# application.net
KiCad netlist of a schematic drawn in EAGLE
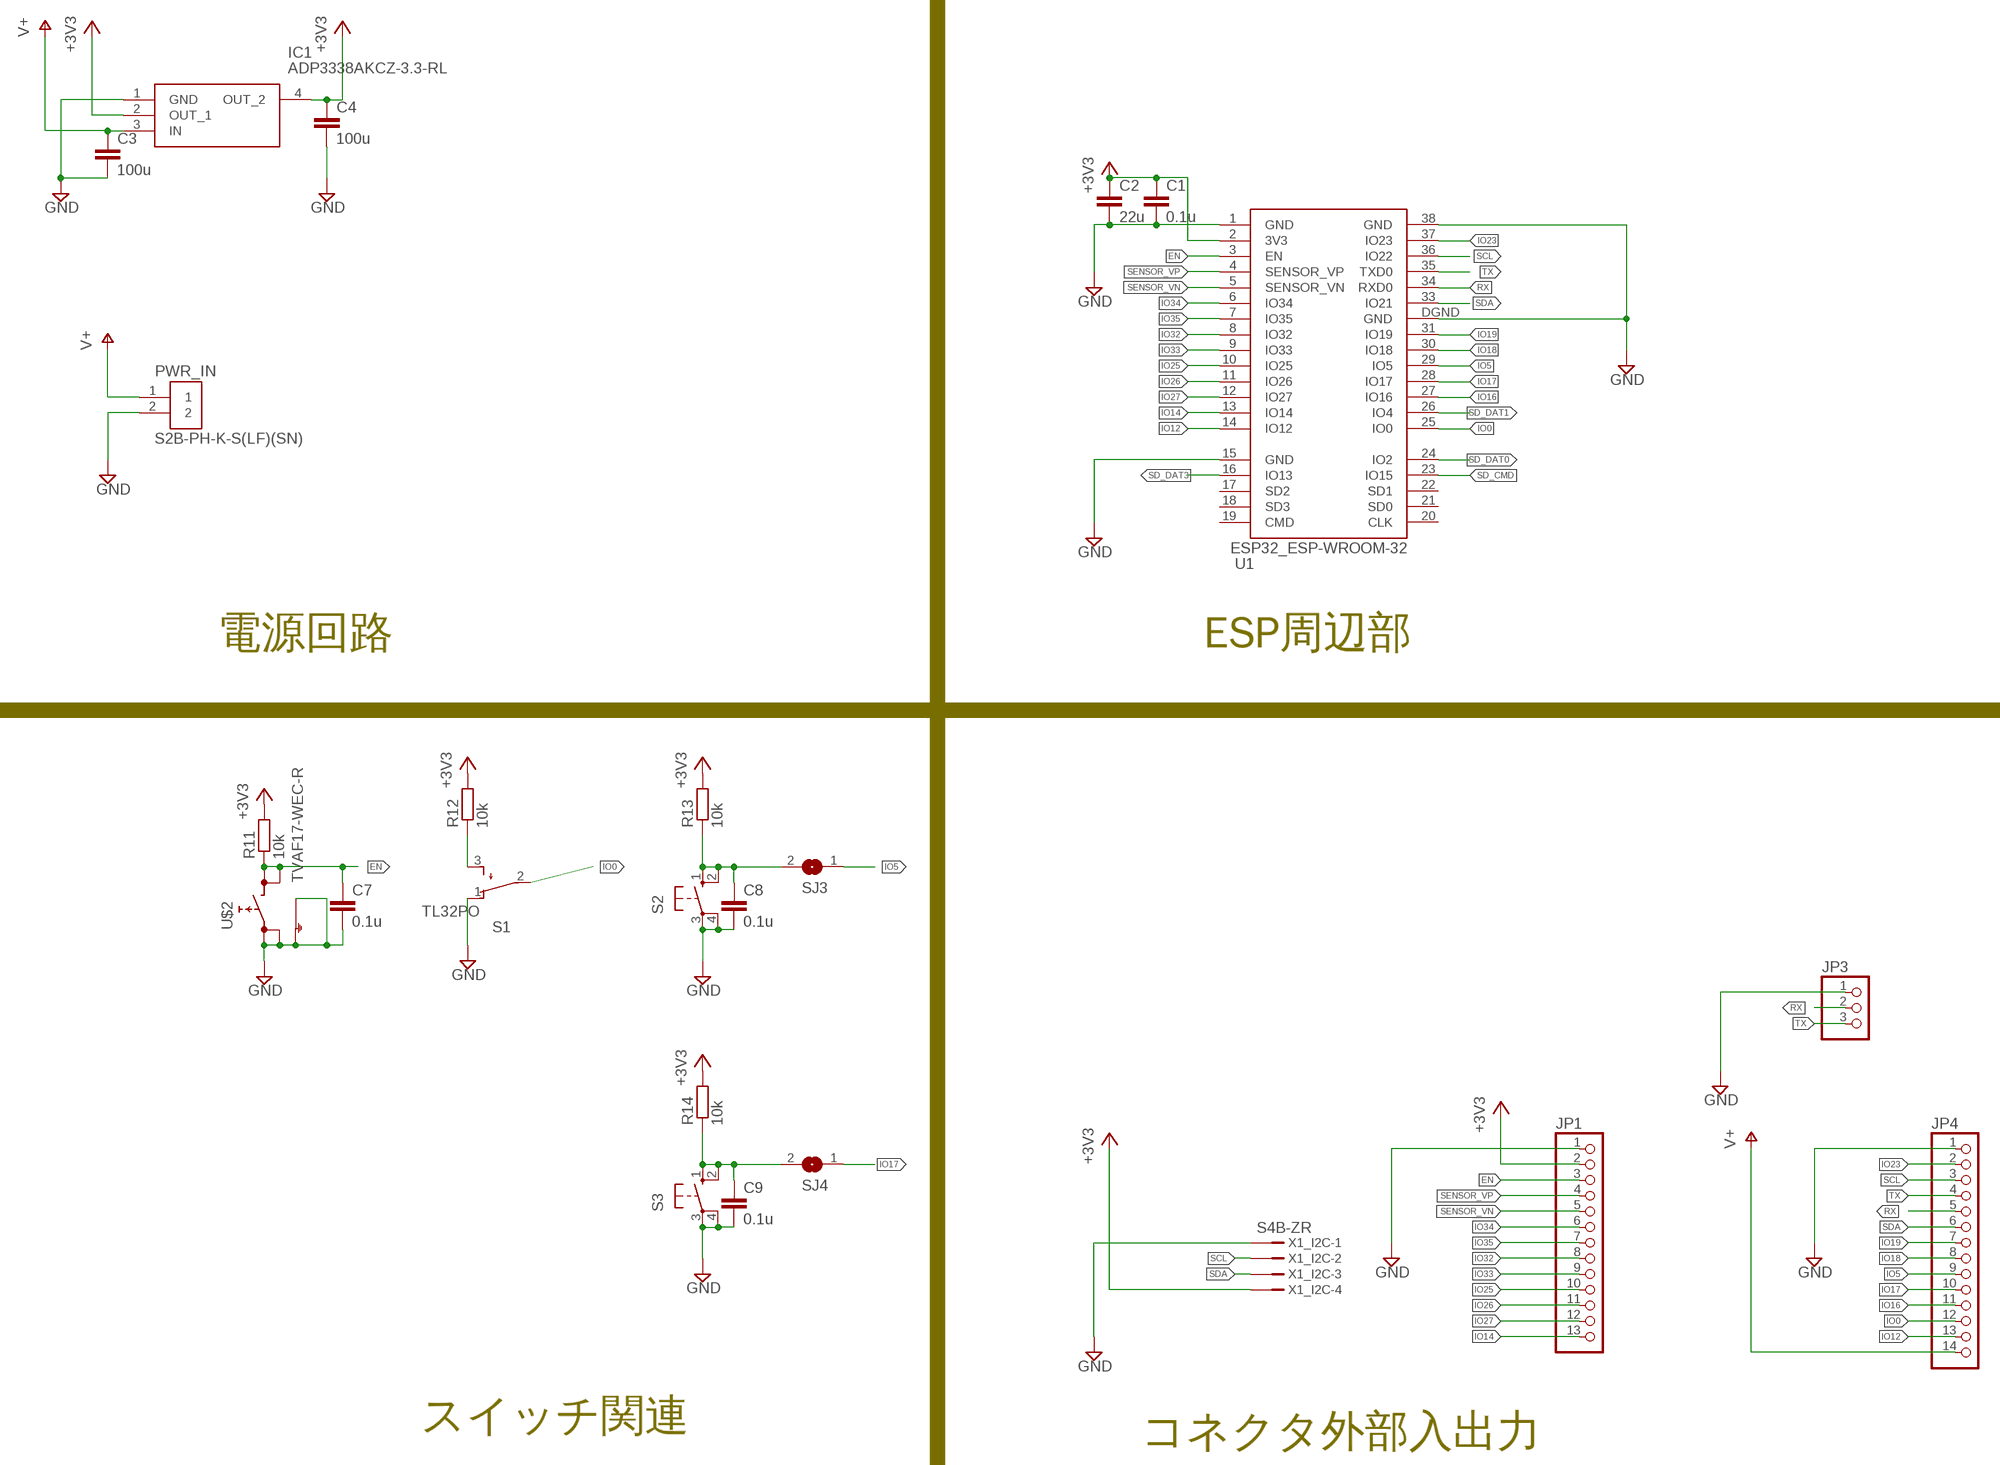
[diagram p0: schematic, sheet 1]

(export (version "E")
  (design (tool "Eeschema 10.0.6"))
  (components
    (comp (ref "C1")
      (value "0.1u")
      (footprint "eagle-import:C0603K")
      (libsource (lib "eagle-import") (part "C-EUC0603K"))
    )
    (comp (ref "C2")
      (value "22u")
      (footprint "eagle-import:C0805")
      (libsource (lib "eagle-import") (part "C-EUC0805"))
    )
    (comp (ref "C3")
      (value "100u")
      (footprint "eagle-import:C1206")
      (libsource (lib "eagle-import") (part "C-EUC1206"))
    )
    (comp (ref "C4")
      (value "100u")
      (footprint "eagle-import:C1206")
      (libsource (lib "eagle-import") (part "C-EUC1206"))
    )
    (comp (ref "C7")
      (value "0.1u")
      (footprint "eagle-import:C0603K")
      (libsource (lib "eagle-import") (part "C-EUC0603K"))
    )
    (comp (ref "C8")
      (value "0.1u")
      (footprint "eagle-import:C0603K")
      (libsource (lib "eagle-import") (part "C-EUC0603K"))
    )
    (comp (ref "C9")
      (value "0.1u")
      (footprint "eagle-import:C0603K")
      (libsource (lib "eagle-import") (part "C-EUC0603K"))
    )
    (comp (ref "IC1")
      (value "ADP3338AKCZ-3.3-RL")
      (footprint "eagle-import:SOT230P700X180-4N")
      (fields (field (name "MOUSER_PART_NUMBER") "584-ADP3338AKCZ3.3R"))
      (libsource (lib "eagle-import") (part "ADP3338AKCZ-3.3-RL"))
    )
    (comp (ref "JP1")
      (value "PINHD-1X13")
      (footprint "eagle-import:1X13")
      (libsource (lib "eagle-import") (part "PINHD-1X13"))
    )
    (comp (ref "JP3")
      (value "PINHD-1X3")
      (footprint "eagle-import:1X03")
      (libsource (lib "eagle-import") (part "PINHD-1X3"))
    )
    (comp (ref "JP4")
      (value "PINHD-1X14")
      (footprint "eagle-import:1X14")
      (libsource (lib "eagle-import") (part "PINHD-1X14"))
    )
    (comp (ref "PWR_IN")
      (value "S2B-PH-K-S(LF)(SN)")
      (footprint "eagle-import:S2B-PH-K-S(LF)(SN)")
      (fields
        (field (name "DIGI_KEY_PART_NUMBER") "455-1719-ND")
        (field (name "MANUFACTURER") "JST Sales America Inc.")
        (field (name "CREATED_BY") "PCBLayout.com")
      )
      (libsource (lib "eagle-import") (part "S2B-PH-K-S(LF)(SN)"))
    )
    (comp (ref "R11")
      (value "10k")
      (footprint "eagle-import:R0603")
      (libsource (lib "eagle-import") (part "R-EU_R0603"))
    )
    (comp (ref "R12")
      (value "10k")
      (footprint "eagle-import:R0603")
      (libsource (lib "eagle-import") (part "R-EU_R0603"))
    )
    (comp (ref "R13")
      (value "10k")
      (footprint "eagle-import:R0603")
      (libsource (lib "eagle-import") (part "R-EU_R0603"))
    )
    (comp (ref "R14")
      (value "10k")
      (footprint "eagle-import:R0603")
      (libsource (lib "eagle-import") (part "R-EU_R0603"))
    )
    (comp (ref "S1")
      (value "TL32PO")
      (footprint "eagle-import:TL3XPO")
      (libsource (lib "eagle-import") (part "TL32PO"))
    )
    (comp (ref "S2")
      (value "10-XX")
      (footprint "eagle-import:B3F-10XX")
      (fields (field (name "MPN") "B3F-1000"))
      (libsource (lib "eagle-import") (part "10-XX"))
    )
    (comp (ref "S3")
      (value "10-XX")
      (footprint "eagle-import:B3F-10XX")
      (fields (field (name "MPN") "B3F-1000"))
      (libsource (lib "eagle-import") (part "10-XX"))
    )
    (comp (ref "SJ3")
      (value "SJW")
      (footprint "eagle-import:SJW")
      (libsource (lib "eagle-import") (part "SJW"))
    )
    (comp (ref "SJ4")
      (value "SJW")
      (footprint "eagle-import:SJW")
      (libsource (lib "eagle-import") (part "SJW"))
    )
    (comp (ref "U$2")
      (value "TVAF17-WEC-R")
      (footprint "eagle-import:TVAF17-WEC-R")
      (libsource (lib "eagle-import") (part "TVAF17-WEC-R"))
    )
    (comp (ref "U1")
      (value "ESP32_ESP-WROOM-32")
      (footprint "eagle-import:ESP32_ESP-WROOM-32")
      (libsource (lib "eagle-import") (part "ESP32_ESP-WROOM-32"))
    )
    (comp (ref "X1_I2C")
      (value "S4B-ZR")
      (footprint "eagle-import:S4B-ZR")
      (fields (field (name "MF") "FARNELL") (field (name "MPN") "S4B-ZR(LF)(SN)"))
      (libsource (lib "eagle-import") (part "?4B-ZRS"))
    )
  )
  (nets
    (net (code "1") (name "+3V3") (class "Default")
      (node (ref "C1") (pin "1") (pinfunction "1_1") (pintype "passive"))
      (node (ref "C2") (pin "1") (pinfunction "1_1") (pintype "passive"))
      (node (ref "C4") (pin "1") (pinfunction "1_1") (pintype "passive"))
      (node (ref "IC1") (pin "2") (pinfunction "OUT_1_2") (pintype "bidirectional"))
      (node (ref "IC1") (pin "4") (pinfunction "OUT_2_4") (pintype "bidirectional"))
      (node (ref "JP1") (pin "2") (pinfunction "2_2") (pintype "passive"))
      (node (ref "R11") (pin "2") (pinfunction "2_2") (pintype "passive"))
      (node (ref "R12") (pin "2") (pinfunction "2_2") (pintype "passive"))
      (node (ref "R13") (pin "2") (pinfunction "2_2") (pintype "passive"))
      (node (ref "R14") (pin "2") (pinfunction "2_2") (pintype "passive"))
      (node (ref "U1") (pin "2") (pinfunction "3V3_2") (pintype "power_in"))
      (node (ref "X1_I2C") (pin "4") (pinfunction "1_4") (pintype "passive"))
    )
    (net (code "2") (name "EN") (class "Default")
      (node (ref "C7") (pin "1") (pinfunction "1_1") (pintype "passive"))
      (node (ref "JP1") (pin "3") (pinfunction "3_3") (pintype "passive"))
      (node (ref "R11") (pin "1") (pinfunction "1_1") (pintype "passive"))
      (node (ref "U$2") (pin "P$3") (pinfunction "3_P$3") (pintype "passive"))
      (node (ref "U$2") (pin "P$4") (pinfunction "4_P$4") (pintype "passive"))
      (node (ref "U1") (pin "3") (pinfunction "EN_3") (pintype "input"))
    )
    (net (code "3") (name "GND") (class "Default")
      (node (ref "C1") (pin "2") (pinfunction "2_2") (pintype "passive"))
      (node (ref "C2") (pin "2") (pinfunction "2_2") (pintype "passive"))
      (node (ref "C3") (pin "2") (pinfunction "2_2") (pintype "passive"))
      (node (ref "C4") (pin "2") (pinfunction "2_2") (pintype "passive"))
      (node (ref "C7") (pin "2") (pinfunction "2_2") (pintype "passive"))
      (node (ref "C8") (pin "2") (pinfunction "2_2") (pintype "passive"))
      (node (ref "C9") (pin "2") (pinfunction "2_2") (pintype "passive"))
      (node (ref "IC1") (pin "1") (pinfunction "GND_1") (pintype "bidirectional"))
      (node (ref "JP1") (pin "1") (pinfunction "1_1") (pintype "passive"))
      (node (ref "JP3") (pin "1") (pinfunction "1_1") (pintype "passive"))
      (node (ref "JP4") (pin "1") (pinfunction "1_1") (pintype "passive"))
      (node (ref "PWR_IN") (pin "2") (pinfunction "2_2") (pintype "passive"))
      (node (ref "S1") (pin "1") (pinfunction "O_1") (pintype "passive"))
      (node (ref "S2") (pin "3") (pinfunction "P_3") (pintype "passive"))
      (node (ref "S2") (pin "4") (pinfunction "P1_4") (pintype "passive"))
      (node (ref "S3") (pin "3") (pinfunction "P_3") (pintype "passive"))
      (node (ref "S3") (pin "4") (pinfunction "P1_4") (pintype "passive"))
      (node (ref "U$2") (pin "P$1") (pinfunction "1_P$1") (pintype "passive"))
      (node (ref "U$2") (pin "P$2") (pinfunction "2_P$2") (pintype "passive"))
      (node (ref "U$2") (pin "P$5") (pinfunction "5_P$5") (pintype "passive"))
      (node (ref "U$2") (pin "P$6") (pinfunction "6_P$6") (pintype "passive"))
      (node (ref "U1") (pin "1") (pinfunction "GND_1") (pintype "power_in"))
      (node (ref "U1") (pin "15") (pinfunction "GND_15") (pintype "power_in"))
      (node (ref "U1") (pin "38") (pinfunction "GND_38") (pintype "power_in"))
      (node (ref "U1") (pin "DGND") (pinfunction "GND_DGND") (pintype "power_in"))
      (node (ref "X1_I2C") (pin "1") (pinfunction "1_1") (pintype "passive"))
    )
    (net (code "4") (name "IO0") (class "Default")
      (node (ref "JP4") (pin "12") (pinfunction "12_12") (pintype "passive"))
      (node (ref "S1") (pin "2") (pinfunction "P_2") (pintype "passive"))
      (node (ref "U1") (pin "25") (pinfunction "IO0_25") (pintype "bidirectional"))
    )
    (net (code "5") (name "IO5") (class "Default")
      (node (ref "JP4") (pin "9") (pinfunction "9_9") (pintype "passive"))
      (node (ref "SJ3") (pin "1") (pinfunction "1_1") (pintype "passive"))
      (node (ref "U1") (pin "29") (pinfunction "IO5_29") (pintype "bidirectional"))
    )
    (net (code "6") (name "IO12") (class "Default")
      (node (ref "JP4") (pin "13") (pinfunction "13_13") (pintype "passive"))
      (node (ref "U1") (pin "14") (pinfunction "IO12_14") (pintype "bidirectional"))
    )
    (net (code "7") (name "IO14") (class "Default")
      (node (ref "JP1") (pin "13") (pinfunction "13_13") (pintype "passive"))
      (node (ref "U1") (pin "13") (pinfunction "IO14_13") (pintype "bidirectional"))
    )
    (net (code "8") (name "IO16") (class "Default")
      (node (ref "JP4") (pin "11") (pinfunction "11_11") (pintype "passive"))
      (node (ref "U1") (pin "27") (pinfunction "IO16_27") (pintype "bidirectional"))
    )
    (net (code "9") (name "IO17") (class "Default")
      (node (ref "JP4") (pin "10") (pinfunction "10_10") (pintype "passive"))
      (node (ref "SJ4") (pin "1") (pinfunction "1_1") (pintype "passive"))
      (node (ref "U1") (pin "28") (pinfunction "IO17_28") (pintype "bidirectional"))
    )
    (net (code "10") (name "IO18") (class "Default")
      (node (ref "JP4") (pin "8") (pinfunction "8_8") (pintype "passive"))
      (node (ref "U1") (pin "30") (pinfunction "IO18_30") (pintype "bidirectional"))
    )
    (net (code "11") (name "IO19") (class "Default")
      (node (ref "JP4") (pin "7") (pinfunction "7_7") (pintype "passive"))
      (node (ref "U1") (pin "31") (pinfunction "IO19_31") (pintype "bidirectional"))
    )
    (net (code "12") (name "IO23") (class "Default")
      (node (ref "JP4") (pin "2") (pinfunction "2_2") (pintype "passive"))
      (node (ref "U1") (pin "37") (pinfunction "IO23_37") (pintype "bidirectional"))
    )
    (net (code "13") (name "IO25") (class "Default")
      (node (ref "JP1") (pin "10") (pinfunction "10_10") (pintype "passive"))
      (node (ref "U1") (pin "10") (pinfunction "IO25_10") (pintype "bidirectional"))
    )
    (net (code "14") (name "IO26") (class "Default")
      (node (ref "JP1") (pin "11") (pinfunction "11_11") (pintype "passive"))
      (node (ref "U1") (pin "11") (pinfunction "IO26_11") (pintype "bidirectional"))
    )
    (net (code "15") (name "IO27") (class "Default")
      (node (ref "JP1") (pin "12") (pinfunction "12_12") (pintype "passive"))
      (node (ref "U1") (pin "12") (pinfunction "IO27_12") (pintype "bidirectional"))
    )
    (net (code "16") (name "IO32") (class "Default")
      (node (ref "JP1") (pin "8") (pinfunction "8_8") (pintype "passive"))
      (node (ref "U1") (pin "8") (pinfunction "IO32_8") (pintype "bidirectional"))
    )
    (net (code "17") (name "IO33") (class "Default")
      (node (ref "JP1") (pin "9") (pinfunction "9_9") (pintype "passive"))
      (node (ref "U1") (pin "9") (pinfunction "IO33_9") (pintype "bidirectional"))
    )
    (net (code "18") (name "IO34") (class "Default")
      (node (ref "JP1") (pin "6") (pinfunction "6_6") (pintype "passive"))
      (node (ref "U1") (pin "6") (pinfunction "IO34_6") (pintype "bidirectional"))
    )
    (net (code "19") (name "IO35") (class "Default")
      (node (ref "JP1") (pin "7") (pinfunction "7_7") (pintype "passive"))
      (node (ref "U1") (pin "7") (pinfunction "IO35_7") (pintype "bidirectional"))
    )
    (net (code "20") (name "Net-(S1-S)") (class "Default")
      (node (ref "R12") (pin "1") (pinfunction "1_1") (pintype "passive"))
      (node (ref "S1") (pin "3") (pinfunction "S_3") (pintype "passive"))
    )
    (net (code "21") (name "Net-(S2-S)") (class "Default")
      (node (ref "C8") (pin "1") (pinfunction "1_1") (pintype "passive"))
      (node (ref "R13") (pin "1") (pinfunction "1_1") (pintype "passive"))
      (node (ref "S2") (pin "1") (pinfunction "S_1") (pintype "passive"))
      (node (ref "S2") (pin "2") (pinfunction "S1_2") (pintype "passive"))
      (node (ref "SJ3") (pin "2") (pinfunction "2_2") (pintype "passive"))
    )
    (net (code "22") (name "Net-(S3-S)") (class "Default")
      (node (ref "C9") (pin "1") (pinfunction "1_1") (pintype "passive"))
      (node (ref "R14") (pin "1") (pinfunction "1_1") (pintype "passive"))
      (node (ref "S3") (pin "1") (pinfunction "S_1") (pintype "passive"))
      (node (ref "S3") (pin "2") (pinfunction "S1_2") (pintype "passive"))
      (node (ref "SJ4") (pin "2") (pinfunction "2_2") (pintype "passive"))
    )
    (net (code "23") (name "RX") (class "Default")
      (node (ref "JP3") (pin "2") (pinfunction "2_2") (pintype "passive"))
      (node (ref "JP4") (pin "5") (pinfunction "5_5") (pintype "passive"))
      (node (ref "U1") (pin "34") (pinfunction "RXD0_34") (pintype "bidirectional"))
    )
    (net (code "24") (name "SCL") (class "Default")
      (node (ref "JP4") (pin "3") (pinfunction "3_3") (pintype "passive"))
      (node (ref "U1") (pin "36") (pinfunction "IO22_36") (pintype "bidirectional"))
      (node (ref "X1_I2C") (pin "2") (pinfunction "1_2") (pintype "passive"))
    )
    (net (code "25") (name "SDA") (class "Default")
      (node (ref "JP4") (pin "6") (pinfunction "6_6") (pintype "passive"))
      (node (ref "U1") (pin "33") (pinfunction "IO21_33") (pintype "bidirectional"))
      (node (ref "X1_I2C") (pin "3") (pinfunction "1_3") (pintype "passive"))
    )
    (net (code "26") (name "SD_CMD") (class "Default")
      (node (ref "U1") (pin "23") (pinfunction "IO15_23") (pintype "bidirectional"))
    )
    (net (code "27") (name "SD_DAT0") (class "Default")
      (node (ref "U1") (pin "24") (pinfunction "IO2_24") (pintype "bidirectional"))
    )
    (net (code "28") (name "SD_DAT1") (class "Default")
      (node (ref "U1") (pin "26") (pinfunction "IO4_26") (pintype "bidirectional"))
    )
    (net (code "29") (name "SD_DAT3") (class "Default")
      (node (ref "U1") (pin "16") (pinfunction "IO13_16") (pintype "bidirectional"))
    )
    (net (code "30") (name "SENSOR_VN") (class "Default")
      (node (ref "JP1") (pin "5") (pinfunction "5_5") (pintype "passive"))
      (node (ref "U1") (pin "5") (pinfunction "SENSOR_VN_5") (pintype "bidirectional"))
    )
    (net (code "31") (name "SENSOR_VP") (class "Default")
      (node (ref "JP1") (pin "4") (pinfunction "4_4") (pintype "passive"))
      (node (ref "U1") (pin "4") (pinfunction "SENSOR_VP_4") (pintype "bidirectional"))
    )
    (net (code "32") (name "TX") (class "Default")
      (node (ref "JP3") (pin "3") (pinfunction "3_3") (pintype "passive"))
      (node (ref "JP4") (pin "4") (pinfunction "4_4") (pintype "passive"))
      (node (ref "U1") (pin "35") (pinfunction "TXD0_35") (pintype "bidirectional"))
    )
    (net (code "33") (name "V+") (class "Default")
      (node (ref "C3") (pin "1") (pinfunction "1_1") (pintype "passive"))
      (node (ref "IC1") (pin "3") (pinfunction "IN_3") (pintype "bidirectional"))
      (node (ref "JP4") (pin "14") (pinfunction "14_14") (pintype "passive"))
      (node (ref "PWR_IN") (pin "1") (pinfunction "1_1") (pintype "passive"))
    )
    (net (code "34") (name "unconnected-(U1-CLK-Pad20)") (class "Default")
      (node (ref "U1") (pin "20") (pinfunction "CLK_20") (pintype "bidirectional"))
    )
    (net (code "35") (name "unconnected-(U1-CMD-Pad19)") (class "Default")
      (node (ref "U1") (pin "19") (pinfunction "CMD_19") (pintype "bidirectional"))
    )
    (net (code "36") (name "unconnected-(U1-SD0-Pad21)") (class "Default")
      (node (ref "U1") (pin "21") (pinfunction "SD0_21") (pintype "bidirectional"))
    )
    (net (code "37") (name "unconnected-(U1-SD1-Pad22)") (class "Default")
      (node (ref "U1") (pin "22") (pinfunction "SD1_22") (pintype "bidirectional"))
    )
    (net (code "38") (name "unconnected-(U1-SD2-Pad17)") (class "Default")
      (node (ref "U1") (pin "17") (pinfunction "SD2_17") (pintype "bidirectional"))
    )
    (net (code "39") (name "unconnected-(U1-SD3-Pad18)") (class "Default")
      (node (ref "U1") (pin "18") (pinfunction "SD3_18") (pintype "bidirectional"))
    )
  )
)
